# CMOS_Clock_5v.net
KiCad netlist of a schematic drawn in EAGLE
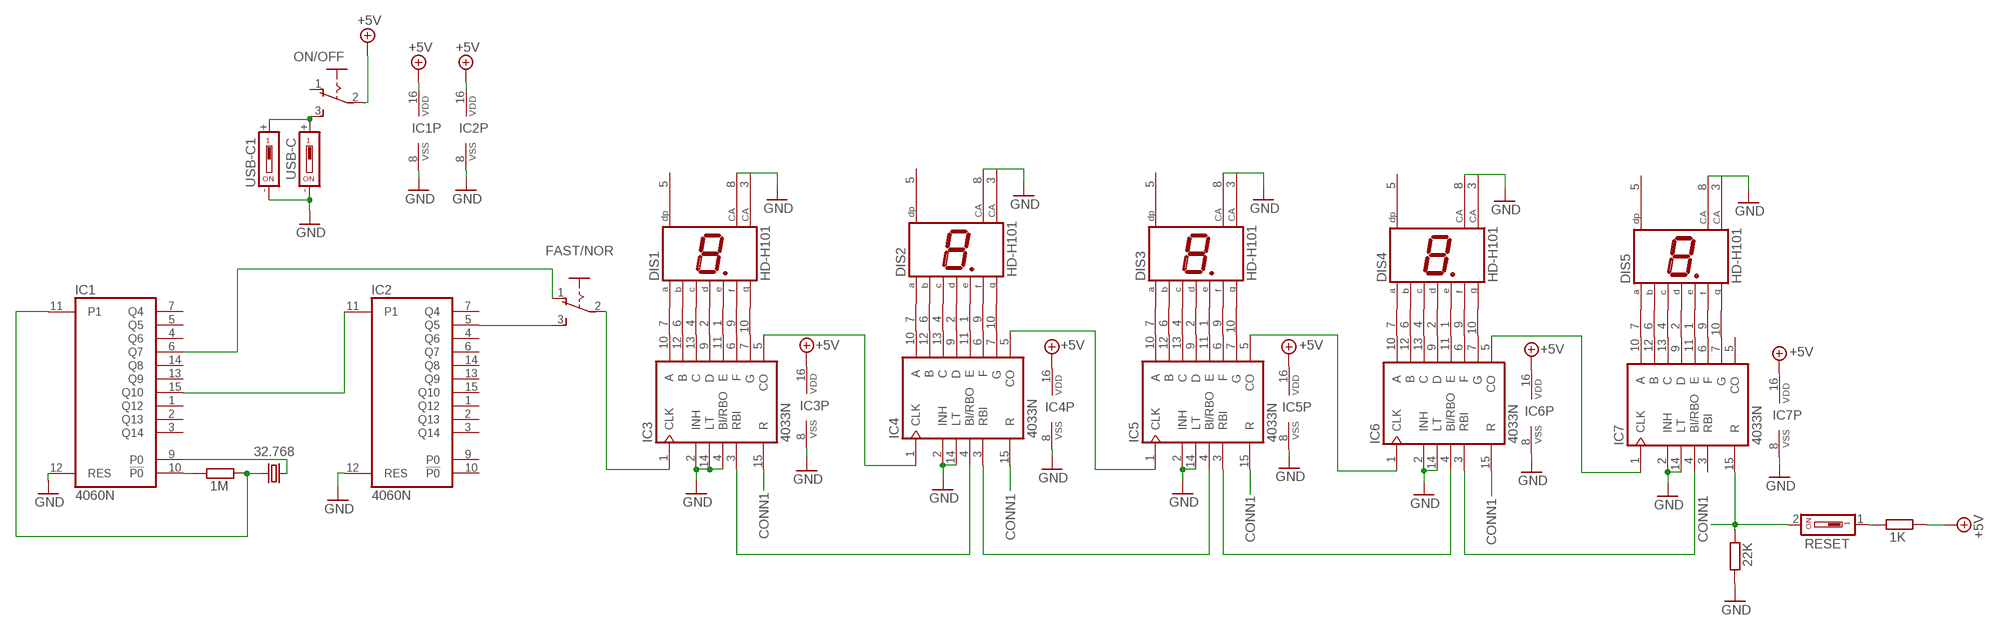
[diagram p0: schematic, sheet 1]

(export (version "E")
  (design (tool "Eeschema 10.0.6"))
  (components
    (comp (ref "DIS1")
      (value "HD-H101")
      (footprint "eagle-import:HDSP-M")
      (libsource (lib "eagle-import") (part "HD-H101"))
    )
    (comp (ref "DIS2")
      (value "HD-H101")
      (footprint "eagle-import:HDSP-M")
      (libsource (lib "eagle-import") (part "HD-H101"))
    )
    (comp (ref "DIS3")
      (value "HD-H101")
      (footprint "eagle-import:HDSP-M")
      (libsource (lib "eagle-import") (part "HD-H101"))
    )
    (comp (ref "DIS4")
      (value "HD-H101")
      (footprint "eagle-import:HDSP-M")
      (libsource (lib "eagle-import") (part "HD-H101"))
    )
    (comp (ref "DIS5")
      (value "HD-H101")
      (footprint "eagle-import:HDSP-M")
      (libsource (lib "eagle-import") (part "HD-H101"))
    )
    (comp (ref "FAST/NOR")
      (value "M251")
      (footprint "eagle-import:M251")
      (libsource (lib "eagle-import") (part "M251"))
    )
    (comp (ref "IC1")
      (value "4060N")
      (footprint "eagle-import:DIL16")
      (libsource (lib "eagle-import") (part "4060N"))
    )
    (comp (ref "IC2")
      (value "4060N")
      (footprint "eagle-import:DIL16")
      (libsource (lib "eagle-import") (part "4060N"))
    )
    (comp (ref "IC3")
      (value "4033N")
      (footprint "eagle-import:DIL16")
      (libsource (lib "eagle-import") (part "4033N"))
    )
    (comp (ref "IC4")
      (value "4033N")
      (footprint "eagle-import:DIL16")
      (libsource (lib "eagle-import") (part "4033N"))
    )
    (comp (ref "IC5")
      (value "4033N")
      (footprint "eagle-import:DIL16")
      (libsource (lib "eagle-import") (part "4033N"))
    )
    (comp (ref "IC6")
      (value "4033N")
      (footprint "eagle-import:DIL16")
      (libsource (lib "eagle-import") (part "4033N"))
    )
    (comp (ref "IC7")
      (value "4033N")
      (footprint "eagle-import:DIL16")
      (libsource (lib "eagle-import") (part "4033N"))
    )
    (comp (ref "ON/OFF")
      (value "M251")
      (footprint "eagle-import:M251")
      (libsource (lib "eagle-import") (part "M251"))
    )
    (comp (ref "Q1")
      (value "32.768")
      (footprint "eagle-import:TC26H")
      (libsource (lib "eagle-import") (part "CRYSTALTC26H"))
    )
    (comp (ref "R1")
      (value "1M")
      (footprint "eagle-import:0207_10")
      (libsource (lib "eagle-import") (part "R-EU_0207/10"))
    )
    (comp (ref "R2")
      (value "1K")
      (footprint "eagle-import:0207_10")
      (libsource (lib "eagle-import") (part "R-EU_0207/10"))
    )
    (comp (ref "R3")
      (value "22K")
      (footprint "eagle-import:0207_10")
      (libsource (lib "eagle-import") (part "R-EU_0207/10"))
    )
    (comp (ref "RESET")
      (value "DS01")
      (footprint "eagle-import:DS-01")
      (libsource (lib "eagle-import") (part "DS01"))
    )
    (comp (ref "USB-C")
      (value "USB-C")
      (footprint "eagle-import:DS-01")
      (libsource (lib "eagle-import") (part "USB-C"))
    )
    (comp (ref "USB-C1")
      (value "USB-C")
      (footprint "eagle-import:DS-01")
      (libsource (lib "eagle-import") (part "USB-C"))
    )
  )
  (nets
    (net (code "1") (name "+5V") (class "Default")
      (node (ref "IC1") (pin "16") (pinfunction "VDD_16") (pintype "power_in"))
      (node (ref "IC2") (pin "16") (pinfunction "VDD_16") (pintype "power_in"))
      (node (ref "IC3") (pin "16") (pinfunction "VDD_16") (pintype "power_in"))
      (node (ref "IC4") (pin "16") (pinfunction "VDD_16") (pintype "power_in"))
      (node (ref "IC5") (pin "16") (pinfunction "VDD_16") (pintype "power_in"))
      (node (ref "IC6") (pin "16") (pinfunction "VDD_16") (pintype "power_in"))
      (node (ref "IC7") (pin "16") (pinfunction "VDD_16") (pintype "power_in"))
      (node (ref "ON/OFF") (pin "2") (pinfunction "P_2") (pintype "passive"))
      (node (ref "R2") (pin "2") (pinfunction "2_2") (pintype "passive"))
    )
    (net (code "2") (name "/CONN1") (class "Default")
      (node (ref "IC3") (pin "15") (pinfunction "R_15") (pintype "input"))
      (node (ref "IC4") (pin "15") (pinfunction "R_15") (pintype "input"))
      (node (ref "IC5") (pin "15") (pinfunction "R_15") (pintype "input"))
      (node (ref "IC6") (pin "15") (pinfunction "R_15") (pintype "input"))
      (node (ref "IC7") (pin "15") (pinfunction "R_15") (pintype "input"))
      (node (ref "R3") (pin "2") (pinfunction "2_2") (pintype "passive"))
      (node (ref "RESET") (pin "2") (pinfunction "2_2") (pintype "passive"))
    )
    (net (code "3") (name "GND") (class "Default")
      (node (ref "DIS1") (pin "3") (pinfunction "CA_3") (pintype "passive"))
      (node (ref "DIS1") (pin "8") (pinfunction "CA_8") (pintype "passive"))
      (node (ref "DIS2") (pin "3") (pinfunction "CA_3") (pintype "passive"))
      (node (ref "DIS2") (pin "8") (pinfunction "CA_8") (pintype "passive"))
      (node (ref "DIS3") (pin "3") (pinfunction "CA_3") (pintype "passive"))
      (node (ref "DIS3") (pin "8") (pinfunction "CA_8") (pintype "passive"))
      (node (ref "DIS4") (pin "3") (pinfunction "CA_3") (pintype "passive"))
      (node (ref "DIS4") (pin "8") (pinfunction "CA_8") (pintype "passive"))
      (node (ref "DIS5") (pin "3") (pinfunction "CA_3") (pintype "passive"))
      (node (ref "DIS5") (pin "8") (pinfunction "CA_8") (pintype "passive"))
      (node (ref "IC1") (pin "12") (pinfunction "RES_12") (pintype "input"))
      (node (ref "IC1") (pin "8") (pinfunction "VSS_8") (pintype "power_in"))
      (node (ref "IC2") (pin "12") (pinfunction "RES_12") (pintype "input"))
      (node (ref "IC2") (pin "8") (pinfunction "VSS_8") (pintype "power_in"))
      (node (ref "IC3") (pin "14") (pinfunction "LT_14") (pintype "input"))
      (node (ref "IC3") (pin "2") (pinfunction "INH_2") (pintype "input"))
      (node (ref "IC3") (pin "4") (pinfunction "BI/RBO_4") (pintype "input"))
      (node (ref "IC3") (pin "8") (pinfunction "VSS_8") (pintype "power_in"))
      (node (ref "IC4") (pin "14") (pinfunction "LT_14") (pintype "input"))
      (node (ref "IC4") (pin "2") (pinfunction "INH_2") (pintype "input"))
      (node (ref "IC4") (pin "8") (pinfunction "VSS_8") (pintype "power_in"))
      (node (ref "IC5") (pin "14") (pinfunction "LT_14") (pintype "input"))
      (node (ref "IC5") (pin "2") (pinfunction "INH_2") (pintype "input"))
      (node (ref "IC5") (pin "8") (pinfunction "VSS_8") (pintype "power_in"))
      (node (ref "IC6") (pin "14") (pinfunction "LT_14") (pintype "input"))
      (node (ref "IC6") (pin "2") (pinfunction "INH_2") (pintype "input"))
      (node (ref "IC6") (pin "8") (pinfunction "VSS_8") (pintype "power_in"))
      (node (ref "IC7") (pin "14") (pinfunction "LT_14") (pintype "input"))
      (node (ref "IC7") (pin "2") (pinfunction "INH_2") (pintype "input"))
      (node (ref "IC7") (pin "8") (pinfunction "VSS_8") (pintype "power_in"))
      (node (ref "R3") (pin "1") (pinfunction "1_1") (pintype "passive"))
      (node (ref "USB-C") (pin "-") (pinfunction "2_-") (pintype "passive"))
      (node (ref "USB-C1") (pin "-") (pinfunction "2_-") (pintype "passive"))
    )
    (net (code "4") (name "Net-(DIS1-A)") (class "Default")
      (node (ref "DIS1") (pin "7") (pinfunction "A_7") (pintype "passive"))
      (node (ref "IC3") (pin "10") (pinfunction "A_10") (pintype "output"))
    )
    (net (code "5") (name "Net-(DIS1-B)") (class "Default")
      (node (ref "DIS1") (pin "6") (pinfunction "B_6") (pintype "passive"))
      (node (ref "IC3") (pin "12") (pinfunction "B_12") (pintype "output"))
    )
    (net (code "6") (name "Net-(DIS1-C)") (class "Default")
      (node (ref "DIS1") (pin "4") (pinfunction "C_4") (pintype "passive"))
      (node (ref "IC3") (pin "13") (pinfunction "C_13") (pintype "output"))
    )
    (net (code "7") (name "Net-(DIS1-D)") (class "Default")
      (node (ref "DIS1") (pin "2") (pinfunction "D_2") (pintype "passive"))
      (node (ref "IC3") (pin "9") (pinfunction "D_9") (pintype "output"))
    )
    (net (code "8") (name "Net-(DIS1-E)") (class "Default")
      (node (ref "DIS1") (pin "1") (pinfunction "E_1") (pintype "passive"))
      (node (ref "IC3") (pin "11") (pinfunction "E_11") (pintype "output"))
    )
    (net (code "9") (name "Net-(DIS1-F)") (class "Default")
      (node (ref "DIS1") (pin "9") (pinfunction "F_9") (pintype "passive"))
      (node (ref "IC3") (pin "6") (pinfunction "F_6") (pintype "output"))
    )
    (net (code "10") (name "Net-(DIS1-G)") (class "Default")
      (node (ref "DIS1") (pin "10") (pinfunction "G_10") (pintype "passive"))
      (node (ref "IC3") (pin "7") (pinfunction "G_7") (pintype "output"))
    )
    (net (code "11") (name "Net-(DIS2-A)") (class "Default")
      (node (ref "DIS2") (pin "7") (pinfunction "A_7") (pintype "passive"))
      (node (ref "IC4") (pin "10") (pinfunction "A_10") (pintype "output"))
    )
    (net (code "12") (name "Net-(DIS2-B)") (class "Default")
      (node (ref "DIS2") (pin "6") (pinfunction "B_6") (pintype "passive"))
      (node (ref "IC4") (pin "12") (pinfunction "B_12") (pintype "output"))
    )
    (net (code "13") (name "Net-(DIS2-C)") (class "Default")
      (node (ref "DIS2") (pin "4") (pinfunction "C_4") (pintype "passive"))
      (node (ref "IC4") (pin "13") (pinfunction "C_13") (pintype "output"))
    )
    (net (code "14") (name "Net-(DIS2-D)") (class "Default")
      (node (ref "DIS2") (pin "2") (pinfunction "D_2") (pintype "passive"))
      (node (ref "IC4") (pin "9") (pinfunction "D_9") (pintype "output"))
    )
    (net (code "15") (name "Net-(DIS2-E)") (class "Default")
      (node (ref "DIS2") (pin "1") (pinfunction "E_1") (pintype "passive"))
      (node (ref "IC4") (pin "11") (pinfunction "E_11") (pintype "output"))
    )
    (net (code "16") (name "Net-(DIS2-F)") (class "Default")
      (node (ref "DIS2") (pin "9") (pinfunction "F_9") (pintype "passive"))
      (node (ref "IC4") (pin "6") (pinfunction "F_6") (pintype "output"))
    )
    (net (code "17") (name "Net-(DIS2-G)") (class "Default")
      (node (ref "DIS2") (pin "10") (pinfunction "G_10") (pintype "passive"))
      (node (ref "IC4") (pin "7") (pinfunction "G_7") (pintype "output"))
    )
    (net (code "18") (name "Net-(DIS3-A)") (class "Default")
      (node (ref "DIS3") (pin "7") (pinfunction "A_7") (pintype "passive"))
      (node (ref "IC5") (pin "10") (pinfunction "A_10") (pintype "output"))
    )
    (net (code "19") (name "Net-(DIS3-B)") (class "Default")
      (node (ref "DIS3") (pin "6") (pinfunction "B_6") (pintype "passive"))
      (node (ref "IC5") (pin "12") (pinfunction "B_12") (pintype "output"))
    )
    (net (code "20") (name "Net-(DIS3-C)") (class "Default")
      (node (ref "DIS3") (pin "4") (pinfunction "C_4") (pintype "passive"))
      (node (ref "IC5") (pin "13") (pinfunction "C_13") (pintype "output"))
    )
    (net (code "21") (name "Net-(DIS3-D)") (class "Default")
      (node (ref "DIS3") (pin "2") (pinfunction "D_2") (pintype "passive"))
      (node (ref "IC5") (pin "9") (pinfunction "D_9") (pintype "output"))
    )
    (net (code "22") (name "Net-(DIS3-E)") (class "Default")
      (node (ref "DIS3") (pin "1") (pinfunction "E_1") (pintype "passive"))
      (node (ref "IC5") (pin "11") (pinfunction "E_11") (pintype "output"))
    )
    (net (code "23") (name "Net-(DIS3-F)") (class "Default")
      (node (ref "DIS3") (pin "9") (pinfunction "F_9") (pintype "passive"))
      (node (ref "IC5") (pin "6") (pinfunction "F_6") (pintype "output"))
    )
    (net (code "24") (name "Net-(DIS3-G)") (class "Default")
      (node (ref "DIS3") (pin "10") (pinfunction "G_10") (pintype "passive"))
      (node (ref "IC5") (pin "7") (pinfunction "G_7") (pintype "output"))
    )
    (net (code "25") (name "Net-(DIS4-A)") (class "Default")
      (node (ref "DIS4") (pin "7") (pinfunction "A_7") (pintype "passive"))
      (node (ref "IC6") (pin "10") (pinfunction "A_10") (pintype "output"))
    )
    (net (code "26") (name "Net-(DIS4-B)") (class "Default")
      (node (ref "DIS4") (pin "6") (pinfunction "B_6") (pintype "passive"))
      (node (ref "IC6") (pin "12") (pinfunction "B_12") (pintype "output"))
    )
    (net (code "27") (name "Net-(DIS4-C)") (class "Default")
      (node (ref "DIS4") (pin "4") (pinfunction "C_4") (pintype "passive"))
      (node (ref "IC6") (pin "13") (pinfunction "C_13") (pintype "output"))
    )
    (net (code "28") (name "Net-(DIS4-D)") (class "Default")
      (node (ref "DIS4") (pin "2") (pinfunction "D_2") (pintype "passive"))
      (node (ref "IC6") (pin "9") (pinfunction "D_9") (pintype "output"))
    )
    (net (code "29") (name "Net-(DIS4-E)") (class "Default")
      (node (ref "DIS4") (pin "1") (pinfunction "E_1") (pintype "passive"))
      (node (ref "IC6") (pin "11") (pinfunction "E_11") (pintype "output"))
    )
    (net (code "30") (name "Net-(DIS4-F)") (class "Default")
      (node (ref "DIS4") (pin "9") (pinfunction "F_9") (pintype "passive"))
      (node (ref "IC6") (pin "6") (pinfunction "F_6") (pintype "output"))
    )
    (net (code "31") (name "Net-(DIS4-G)") (class "Default")
      (node (ref "DIS4") (pin "10") (pinfunction "G_10") (pintype "passive"))
      (node (ref "IC6") (pin "7") (pinfunction "G_7") (pintype "output"))
    )
    (net (code "32") (name "Net-(DIS5-A)") (class "Default")
      (node (ref "DIS5") (pin "7") (pinfunction "A_7") (pintype "passive"))
      (node (ref "IC7") (pin "10") (pinfunction "A_10") (pintype "output"))
    )
    (net (code "33") (name "Net-(DIS5-B)") (class "Default")
      (node (ref "DIS5") (pin "6") (pinfunction "B_6") (pintype "passive"))
      (node (ref "IC7") (pin "12") (pinfunction "B_12") (pintype "output"))
    )
    (net (code "34") (name "Net-(DIS5-C)") (class "Default")
      (node (ref "DIS5") (pin "4") (pinfunction "C_4") (pintype "passive"))
      (node (ref "IC7") (pin "13") (pinfunction "C_13") (pintype "output"))
    )
    (net (code "35") (name "Net-(DIS5-D)") (class "Default")
      (node (ref "DIS5") (pin "2") (pinfunction "D_2") (pintype "passive"))
      (node (ref "IC7") (pin "9") (pinfunction "D_9") (pintype "output"))
    )
    (net (code "36") (name "Net-(DIS5-E)") (class "Default")
      (node (ref "DIS5") (pin "1") (pinfunction "E_1") (pintype "passive"))
      (node (ref "IC7") (pin "11") (pinfunction "E_11") (pintype "output"))
    )
    (net (code "37") (name "Net-(DIS5-F)") (class "Default")
      (node (ref "DIS5") (pin "9") (pinfunction "F_9") (pintype "passive"))
      (node (ref "IC7") (pin "6") (pinfunction "F_6") (pintype "output"))
    )
    (net (code "38") (name "Net-(DIS5-G)") (class "Default")
      (node (ref "DIS5") (pin "10") (pinfunction "G_10") (pintype "passive"))
      (node (ref "IC7") (pin "7") (pinfunction "G_7") (pintype "output"))
    )
    (net (code "39") (name "Net-(FAST/NOR-O)") (class "Default")
      (node (ref "FAST/NOR") (pin "1") (pinfunction "O_1") (pintype "passive"))
      (node (ref "IC1") (pin "6") (pinfunction "Q7_6") (pintype "output"))
    )
    (net (code "40") (name "Net-(FAST/NOR-P)") (class "Default")
      (node (ref "FAST/NOR") (pin "2") (pinfunction "P_2") (pintype "passive"))
      (node (ref "IC3") (pin "1") (pinfunction "CLK_1") (pintype "input"))
    )
    (net (code "41") (name "Net-(FAST/NOR-S)") (class "Default")
      (node (ref "FAST/NOR") (pin "3") (pinfunction "S_3") (pintype "passive"))
      (node (ref "IC2") (pin "5") (pinfunction "Q5_5") (pintype "output"))
    )
    (net (code "42") (name "Net-(IC1A-P0)") (class "Default")
      (node (ref "IC1") (pin "9") (pinfunction "P0_9") (pintype "output"))
      (node (ref "Q1") (pin "2") (pinfunction "2_2") (pintype "passive"))
    )
    (net (code "43") (name "Net-(IC1A-P1)") (class "Default")
      (node (ref "IC1") (pin "11") (pinfunction "P1_11") (pintype "input"))
      (node (ref "Q1") (pin "1") (pinfunction "1_1") (pintype "passive"))
      (node (ref "R1") (pin "2") (pinfunction "2_2") (pintype "passive"))
    )
    (net (code "44") (name "Net-(IC1A-Q10)") (class "Default")
      (node (ref "IC1") (pin "15") (pinfunction "Q10_15") (pintype "output"))
      (node (ref "IC2") (pin "11") (pinfunction "P1_11") (pintype "input"))
    )
    (net (code "45") (name "Net-(IC1A-~{P0})") (class "Default")
      (node (ref "IC1") (pin "10") (pinfunction "~{P0}_10") (pintype "output"))
      (node (ref "R1") (pin "1") (pinfunction "1_1") (pintype "passive"))
    )
    (net (code "46") (name "Net-(IC3A-CO)") (class "Default")
      (node (ref "IC3") (pin "5") (pinfunction "CO_5") (pintype "output"))
      (node (ref "IC4") (pin "1") (pinfunction "CLK_1") (pintype "input"))
    )
    (net (code "47") (name "Net-(IC3A-RBI)") (class "Default")
      (node (ref "IC3") (pin "3") (pinfunction "RBI_3") (pintype "input"))
      (node (ref "IC4") (pin "4") (pinfunction "BI/RBO_4") (pintype "input"))
    )
    (net (code "48") (name "Net-(IC4A-CO)") (class "Default")
      (node (ref "IC4") (pin "5") (pinfunction "CO_5") (pintype "output"))
      (node (ref "IC5") (pin "1") (pinfunction "CLK_1") (pintype "input"))
    )
    (net (code "49") (name "Net-(IC4A-RBI)") (class "Default")
      (node (ref "IC4") (pin "3") (pinfunction "RBI_3") (pintype "input"))
      (node (ref "IC5") (pin "4") (pinfunction "BI/RBO_4") (pintype "input"))
    )
    (net (code "50") (name "Net-(IC5A-CO)") (class "Default")
      (node (ref "IC5") (pin "5") (pinfunction "CO_5") (pintype "output"))
      (node (ref "IC6") (pin "1") (pinfunction "CLK_1") (pintype "input"))
    )
    (net (code "51") (name "Net-(IC5A-RBI)") (class "Default")
      (node (ref "IC5") (pin "3") (pinfunction "RBI_3") (pintype "input"))
      (node (ref "IC6") (pin "4") (pinfunction "BI/RBO_4") (pintype "input"))
    )
    (net (code "52") (name "Net-(IC6A-CO)") (class "Default")
      (node (ref "IC6") (pin "5") (pinfunction "CO_5") (pintype "output"))
      (node (ref "IC7") (pin "1") (pinfunction "CLK_1") (pintype "input"))
    )
    (net (code "53") (name "Net-(IC6A-RBI)") (class "Default")
      (node (ref "IC6") (pin "3") (pinfunction "RBI_3") (pintype "input"))
      (node (ref "IC7") (pin "4") (pinfunction "BI/RBO_4") (pintype "input"))
    )
    (net (code "54") (name "Net-(ON/OFF-S)") (class "Default")
      (node (ref "ON/OFF") (pin "3") (pinfunction "S_3") (pintype "passive"))
      (node (ref "USB-C") (pin "+") (pinfunction "1_+") (pintype "passive"))
      (node (ref "USB-C1") (pin "+") (pinfunction "1_+") (pintype "passive"))
    )
    (net (code "55") (name "Net-(R2-Pad1)") (class "Default")
      (node (ref "R2") (pin "1") (pinfunction "1_1") (pintype "passive"))
      (node (ref "RESET") (pin "1") (pinfunction "1_1") (pintype "passive"))
    )
    (net (code "56") (name "unconnected-(DIS1-DP-Pad5)") (class "Default")
      (node (ref "DIS1") (pin "5") (pinfunction "DP_5") (pintype "passive"))
    )
    (net (code "57") (name "unconnected-(DIS2-DP-Pad5)") (class "Default")
      (node (ref "DIS2") (pin "5") (pinfunction "DP_5") (pintype "passive"))
    )
    (net (code "58") (name "unconnected-(DIS3-DP-Pad5)") (class "Default")
      (node (ref "DIS3") (pin "5") (pinfunction "DP_5") (pintype "passive"))
    )
    (net (code "59") (name "unconnected-(DIS4-DP-Pad5)") (class "Default")
      (node (ref "DIS4") (pin "5") (pinfunction "DP_5") (pintype "passive"))
    )
    (net (code "60") (name "unconnected-(DIS5-DP-Pad5)") (class "Default")
      (node (ref "DIS5") (pin "5") (pinfunction "DP_5") (pintype "passive"))
    )
    (net (code "61") (name "unconnected-(IC1A-Q4-Pad7)") (class "Default")
      (node (ref "IC1") (pin "7") (pinfunction "Q4_7") (pintype "output"))
    )
    (net (code "62") (name "unconnected-(IC1A-Q5-Pad5)") (class "Default")
      (node (ref "IC1") (pin "5") (pinfunction "Q5_5") (pintype "output"))
    )
    (net (code "63") (name "unconnected-(IC1A-Q6-Pad4)") (class "Default")
      (node (ref "IC1") (pin "4") (pinfunction "Q6_4") (pintype "output"))
    )
    (net (code "64") (name "unconnected-(IC1A-Q8-Pad14)") (class "Default")
      (node (ref "IC1") (pin "14") (pinfunction "Q8_14") (pintype "output"))
    )
    (net (code "65") (name "unconnected-(IC1A-Q9-Pad13)") (class "Default")
      (node (ref "IC1") (pin "13") (pinfunction "Q9_13") (pintype "output"))
    )
    (net (code "66") (name "unconnected-(IC1A-Q12-Pad1)") (class "Default")
      (node (ref "IC1") (pin "1") (pinfunction "Q12_1") (pintype "output"))
    )
    (net (code "67") (name "unconnected-(IC1A-Q13-Pad2)") (class "Default")
      (node (ref "IC1") (pin "2") (pinfunction "Q13_2") (pintype "output"))
    )
    (net (code "68") (name "unconnected-(IC1A-Q14-Pad3)") (class "Default")
      (node (ref "IC1") (pin "3") (pinfunction "Q14_3") (pintype "output"))
    )
    (net (code "69") (name "unconnected-(IC2A-P0-Pad9)") (class "Default")
      (node (ref "IC2") (pin "9") (pinfunction "P0_9") (pintype "output"))
    )
    (net (code "70") (name "unconnected-(IC2A-Q4-Pad7)") (class "Default")
      (node (ref "IC2") (pin "7") (pinfunction "Q4_7") (pintype "output"))
    )
    (net (code "71") (name "unconnected-(IC2A-Q6-Pad4)") (class "Default")
      (node (ref "IC2") (pin "4") (pinfunction "Q6_4") (pintype "output"))
    )
    (net (code "72") (name "unconnected-(IC2A-Q7-Pad6)") (class "Default")
      (node (ref "IC2") (pin "6") (pinfunction "Q7_6") (pintype "output"))
    )
    (net (code "73") (name "unconnected-(IC2A-Q8-Pad14)") (class "Default")
      (node (ref "IC2") (pin "14") (pinfunction "Q8_14") (pintype "output"))
    )
    (net (code "74") (name "unconnected-(IC2A-Q9-Pad13)") (class "Default")
      (node (ref "IC2") (pin "13") (pinfunction "Q9_13") (pintype "output"))
    )
    (net (code "75") (name "unconnected-(IC2A-Q10-Pad15)") (class "Default")
      (node (ref "IC2") (pin "15") (pinfunction "Q10_15") (pintype "output"))
    )
    (net (code "76") (name "unconnected-(IC2A-Q12-Pad1)") (class "Default")
      (node (ref "IC2") (pin "1") (pinfunction "Q12_1") (pintype "output"))
    )
    (net (code "77") (name "unconnected-(IC2A-Q13-Pad2)") (class "Default")
      (node (ref "IC2") (pin "2") (pinfunction "Q13_2") (pintype "output"))
    )
    (net (code "78") (name "unconnected-(IC2A-Q14-Pad3)") (class "Default")
      (node (ref "IC2") (pin "3") (pinfunction "Q14_3") (pintype "output"))
    )
    (net (code "79") (name "unconnected-(IC2A-~{P0}-Pad10)") (class "Default")
      (node (ref "IC2") (pin "10") (pinfunction "~{P0}_10") (pintype "output"))
    )
    (net (code "80") (name "unconnected-(IC7A-CO-Pad5)") (class "Default")
      (node (ref "IC7") (pin "5") (pinfunction "CO_5") (pintype "output"))
    )
    (net (code "81") (name "unconnected-(IC7A-RBI-Pad3)") (class "Default")
      (node (ref "IC7") (pin "3") (pinfunction "RBI_3") (pintype "input"))
    )
    (net (code "82") (name "unconnected-(ON/OFF-O-Pad1)") (class "Default")
      (node (ref "ON/OFF") (pin "1") (pinfunction "O_1") (pintype "passive"))
    )
  )
)
